# Explore_Labs_GPS_Receiver_ublox_MAX-M8Q.net
KiCad netlist of a schematic drawn in EAGLE
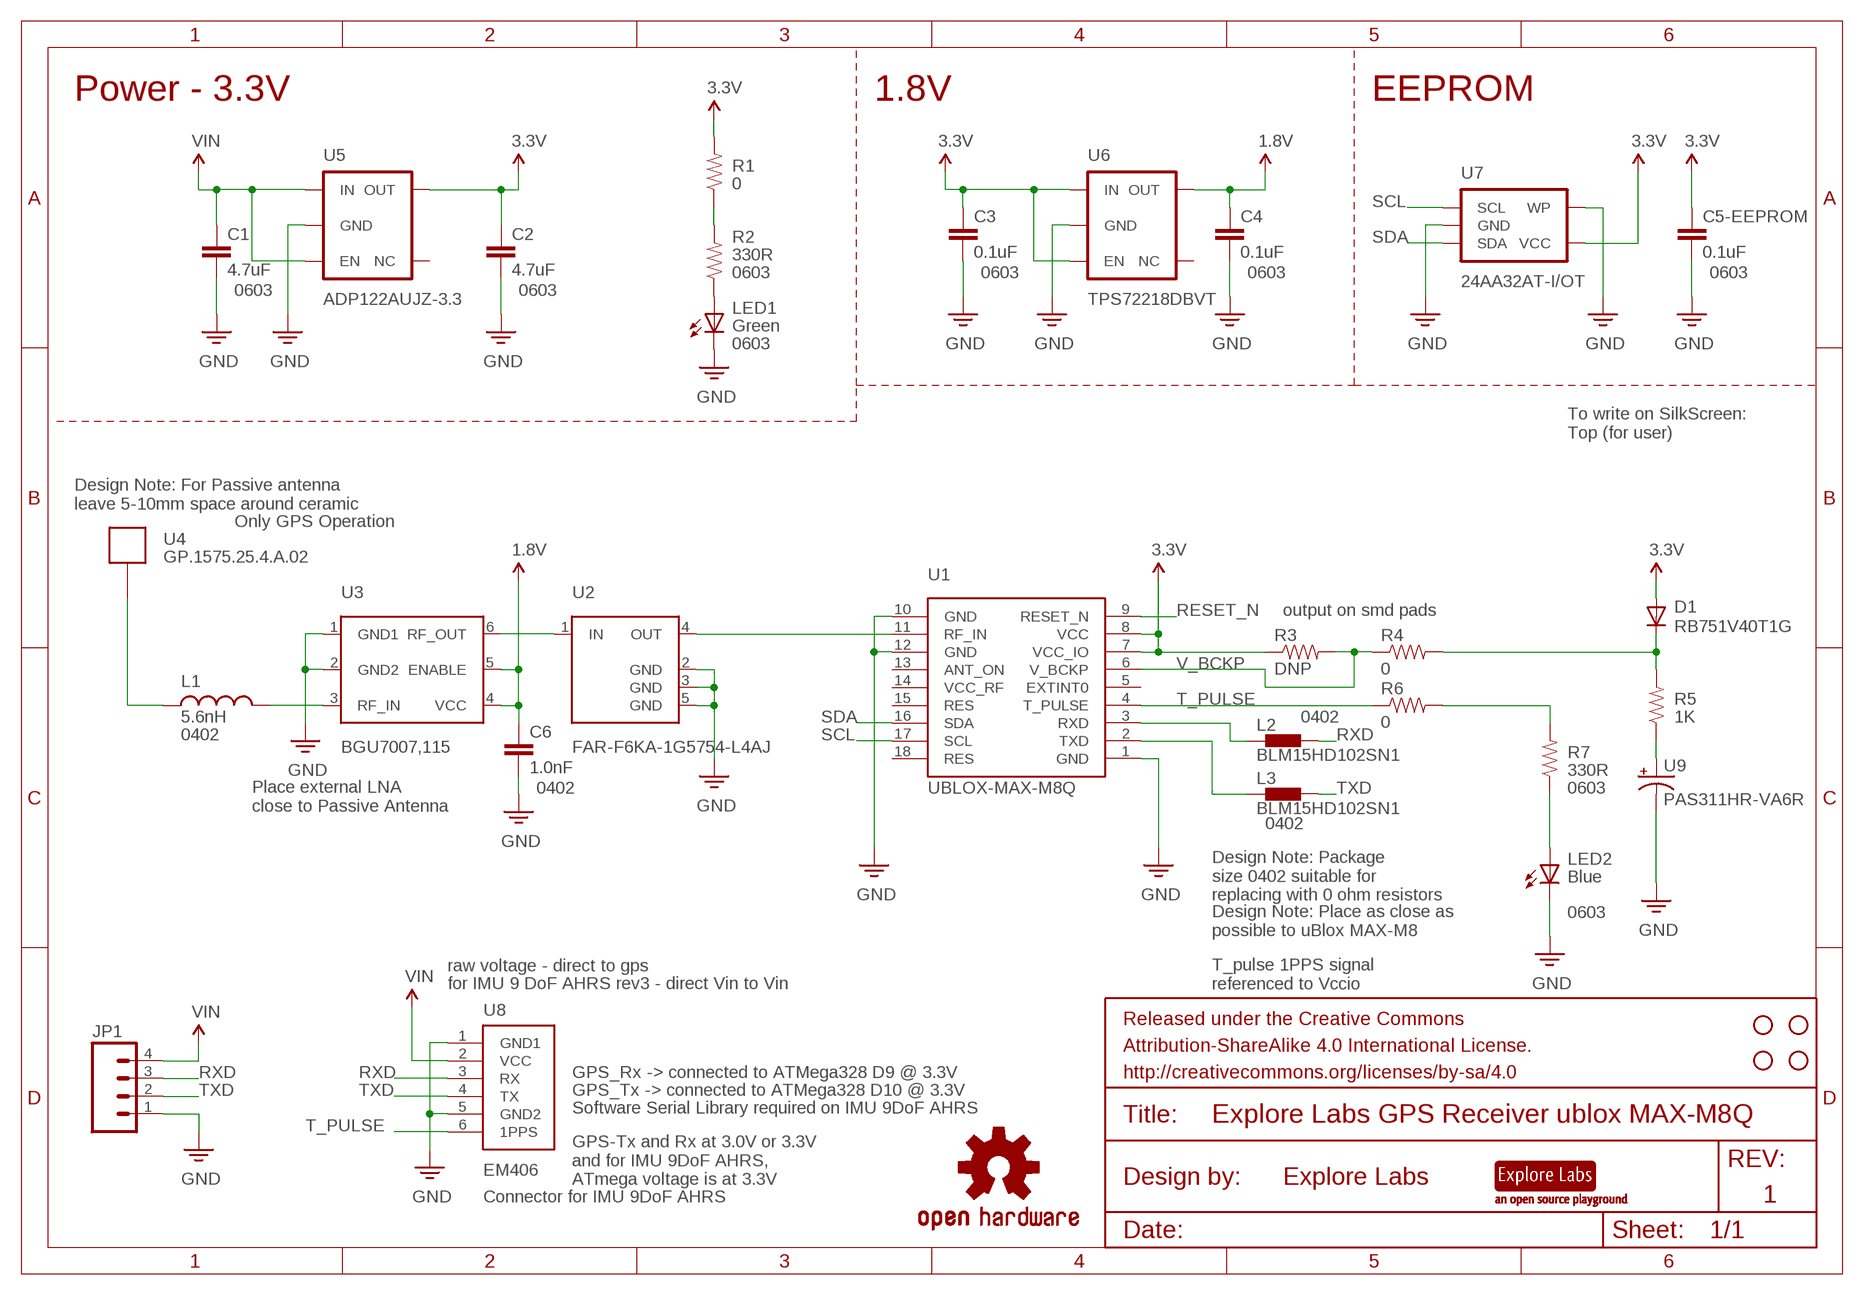
[diagram p0: schematic, sheet 1]

(export (version "E")
  (design (tool "Eeschema 10.0.6"))
  (components
    (comp (ref "C1")
      (value "4.7uF")
      (footprint "eagle-import:0603-CAP")
      (libsource (lib "eagle-import") (part "CAP0603-CAP"))
    )
    (comp (ref "C2")
      (value "4.7uF")
      (footprint "eagle-import:0603-CAP")
      (libsource (lib "eagle-import") (part "CAP0603-CAP"))
    )
    (comp (ref "C3")
      (value "0.1uF")
      (footprint "eagle-import:0603-CAP")
      (libsource (lib "eagle-import") (part "CAP0603-CAP"))
    )
    (comp (ref "C4")
      (value "0.1uF")
      (footprint "eagle-import:0603-CAP")
      (libsource (lib "eagle-import") (part "CAP0603-CAP"))
    )
    (comp (ref "C5-EEPROM")
      (value "0.1uF")
      (footprint "eagle-import:0603-CAP")
      (libsource (lib "eagle-import") (part "CAP0603-CAP"))
    )
    (comp (ref "C6")
      (value "1.0nF")
      (footprint "eagle-import:0402-CAP")
      (libsource (lib "eagle-import") (part "1.0UF-16V-10%(0402)"))
    )
    (comp (ref "D1")
      (value "RB751V40T1G")
      (footprint "eagle-import:SOD-323")
      (libsource (lib "eagle-import") (part "DIODESOD"))
    )
    (comp (ref "JP1")
      (value "M04PTH")
      (footprint "eagle-import:1X04")
      (libsource (lib "eagle-import") (part "M04PTH"))
    )
    (comp (ref "L1")
      (value "5.6nH")
      (footprint "eagle-import:C0402")
      (libsource (lib "eagle-import") (part "INDUCTOR0402"))
    )
    (comp (ref "L2")
      (value "BLM15HD102SN1")
      (footprint "eagle-import:0402-FERRITE")
      (libsource (lib "eagle-import") (part "BLM15HSN1D102"))
    )
    (comp (ref "L3")
      (value "BLM15HD102SN1")
      (footprint "eagle-import:0402-FERRITE")
      (libsource (lib "eagle-import") (part "BLM15HSN1D102"))
    )
    (comp (ref "LED1")
      (value "Green")
      (footprint "eagle-import:CHIP-LED0603")
      (libsource (lib "eagle-import") (part "LEDCHIP-LED0603"))
    )
    (comp (ref "LED2")
      (value "Blue")
      (footprint "eagle-import:CHIP-LED0603")
      (libsource (lib "eagle-import") (part "LEDCHIP-LED0603"))
    )
    (comp (ref "LOGO1")
      (value "OSHW-LOGOTOP")
      (footprint "eagle-import:OSHW-LOGO-M-TOP")
      (libsource (lib "eagle-import") (part "OSHW-LOGOTOP"))
    )
    (comp (ref "LOGO2")
      (value "OSHW-LOGOBOTTOM")
      (footprint "eagle-import:OSHW-LOGO-M-BOTTOM")
      (libsource (lib "eagle-import") (part "OSHW-LOGOBOTTOM"))
    )
    (comp (ref "R1")
      (value "0")
      (footprint "eagle-import:0603-RES")
      (libsource (lib "eagle-import") (part "RESISTOR0603-RES"))
    )
    (comp (ref "R2")
      (value "330R")
      (footprint "eagle-import:0603-RES")
      (libsource (lib "eagle-import") (part "RESISTOR0603-RES"))
    )
    (comp (ref "R3")
      (value "DNP")
      (footprint "eagle-import:0603-RES")
      (libsource (lib "eagle-import") (part "RESISTOR0603-RES"))
    )
    (comp (ref "R4")
      (value "0")
      (footprint "eagle-import:0603-RES")
      (libsource (lib "eagle-import") (part "RESISTOR0603-RES"))
    )
    (comp (ref "R5")
      (value "1K")
      (footprint "eagle-import:0603-RES")
      (libsource (lib "eagle-import") (part "RESISTOR0603-RES"))
    )
    (comp (ref "R6")
      (value "0")
      (footprint "eagle-import:0603-RES")
      (libsource (lib "eagle-import") (part "RESISTOR0603-RES"))
    )
    (comp (ref "R7")
      (value "330R")
      (footprint "eagle-import:0603-RES")
      (libsource (lib "eagle-import") (part "RESISTOR0603-RES"))
    )
    (comp (ref "STANDOFF1")
      (value "STAND-OFF")
      (footprint "eagle-import:STAND-OFF")
      (libsource (lib "eagle-import") (part "STAND-OFF"))
    )
    (comp (ref "STANDOFF2")
      (value "STAND-OFF")
      (footprint "eagle-import:STAND-OFF")
      (libsource (lib "eagle-import") (part "STAND-OFF"))
    )
    (comp (ref "STANDOFF3")
      (value "STAND-OFF")
      (footprint "eagle-import:STAND-OFF")
      (libsource (lib "eagle-import") (part "STAND-OFF"))
    )
    (comp (ref "STANDOFF4")
      (value "STAND-OFF")
      (footprint "eagle-import:STAND-OFF")
      (libsource (lib "eagle-import") (part "STAND-OFF"))
    )
    (comp (ref "U$9")
      (value "EXPLORE-LABS-LOGO")
      (footprint "eagle-import:EXPLORE-LABS-LOGO-TOP")
      (libsource (lib "eagle-import") (part "EXPLORE-LABS-LOGO"))
    )
    (comp (ref "U1")
      (value "UBLOX-MAX-M8Q")
      (footprint "eagle-import:UBLOX-MAX-M8")
      (libsource (lib "eagle-import") (part "UBLOX-MAX-M8Q"))
    )
    (comp (ref "U2")
      (value "FAR-F6KA-1G5754-L4AJ")
      (footprint "eagle-import:QCS5E")
      (libsource (lib "eagle-import") (part "FAR-F6KA-1G5754-L4AJ"))
    )
    (comp (ref "U3")
      (value "BGU7007,115")
      (footprint "eagle-import:SOT886")
      (libsource (lib "eagle-import") (part "BGU7007,115"))
    )
    (comp (ref "U4")
      (value "GP.1575.25.4.A.02")
      (footprint "eagle-import:GP.1575.25.4.A.02")
      (libsource (lib "eagle-import") (part "GP.1575.25.4.A.02"))
    )
    (comp (ref "U5")
      (value "ADP122AUJZ-3.3")
      (footprint "eagle-import:SOT-23-5")
      (libsource (lib "eagle-import") (part "ADP122AUJZ-3.3"))
    )
    (comp (ref "U6")
      (value "TPS72218DBVT")
      (footprint "eagle-import:SOT-23-5")
      (libsource (lib "eagle-import") (part "TPS72218DBVT"))
    )
    (comp (ref "U7")
      (value "24AA32AT-I/OT")
      (footprint "eagle-import:SOT-23-5")
      (libsource (lib "eagle-import") (part "24AA32AT-I/OT"))
    )
    (comp (ref "U8")
      (value "EM406")
      (footprint "eagle-import:EM406")
      (libsource (lib "eagle-import") (part "EM406"))
    )
    (comp (ref "U9")
      (value "PAS311HR-VA6R")
      (footprint "eagle-import:PA311")
      (libsource (lib "eagle-import") (part "PAS311HR-VA6R"))
    )
  )
  (nets
    (net (code "1") (name "/RESET_N") (class "Default")
      (node (ref "U1") (pin "9") (pinfunction "RESET_N_9") (pintype "bidirectional"))
    )
    (net (code "2") (name "/RXD") (class "Default")
      (node (ref "JP1") (pin "3") (pinfunction "3_3") (pintype "passive"))
      (node (ref "L2") (pin "2") (pinfunction "2_2") (pintype "passive"))
      (node (ref "U8") (pin "3") (pinfunction "RX_3") (pintype "bidirectional"))
    )
    (net (code "3") (name "/SCL") (class "Default")
      (node (ref "U1") (pin "17") (pinfunction "SCL_17") (pintype "bidirectional"))
      (node (ref "U7") (pin "1") (pinfunction "SCL_1") (pintype "input"))
    )
    (net (code "4") (name "/SDA") (class "Default")
      (node (ref "U1") (pin "16") (pinfunction "SDA_16") (pintype "bidirectional"))
      (node (ref "U7") (pin "3") (pinfunction "SDA_3") (pintype "bidirectional"))
    )
    (net (code "5") (name "/TXD") (class "Default")
      (node (ref "JP1") (pin "2") (pinfunction "2_2") (pintype "passive"))
      (node (ref "L3") (pin "2") (pinfunction "2_2") (pintype "passive"))
      (node (ref "U8") (pin "4") (pinfunction "TX_4") (pintype "bidirectional"))
    )
    (net (code "6") (name "/T_PULSE") (class "Default")
      (node (ref "R6") (pin "1") (pinfunction "1_1") (pintype "passive"))
      (node (ref "U1") (pin "4") (pinfunction "T_PULSE_4") (pintype "bidirectional"))
      (node (ref "U8") (pin "6") (pinfunction "1PPS_6") (pintype "bidirectional"))
    )
    (net (code "7") (name "/V_BCKP") (class "Default")
      (node (ref "R3") (pin "2") (pinfunction "2_2") (pintype "passive"))
      (node (ref "R4") (pin "1") (pinfunction "1_1") (pintype "passive"))
      (node (ref "U1") (pin "6") (pinfunction "V_BCKP_6") (pintype "bidirectional"))
    )
    (net (code "8") (name "1.8V") (class "Default")
      (node (ref "C4") (pin "1") (pinfunction "1_1") (pintype "passive"))
      (node (ref "C6") (pin "1") (pinfunction "1_1") (pintype "passive"))
      (node (ref "U3") (pin "4") (pinfunction "VCC_4") (pintype "bidirectional"))
      (node (ref "U3") (pin "5") (pinfunction "ENABLE_5") (pintype "bidirectional"))
      (node (ref "U6") (pin "5") (pinfunction "OUT_5") (pintype "power_in"))
    )
    (net (code "9") (name "3.3V") (class "Default")
      (node (ref "C2") (pin "1") (pinfunction "1_1") (pintype "passive"))
      (node (ref "C3") (pin "1") (pinfunction "1_1") (pintype "passive"))
      (node (ref "C5-EEPROM") (pin "1") (pinfunction "1_1") (pintype "passive"))
      (node (ref "D1") (pin "2") (pinfunction "A_2") (pintype "passive"))
      (node (ref "R1") (pin "2") (pinfunction "2_2") (pintype "passive"))
      (node (ref "R3") (pin "1") (pinfunction "1_1") (pintype "passive"))
      (node (ref "U1") (pin "7") (pinfunction "VCC_IO_7") (pintype "bidirectional"))
      (node (ref "U1") (pin "8") (pinfunction "VCC_8") (pintype "bidirectional"))
      (node (ref "U5") (pin "5") (pinfunction "OUT_5") (pintype "power_in"))
      (node (ref "U6") (pin "1") (pinfunction "IN_1") (pintype "power_in"))
      (node (ref "U6") (pin "3") (pinfunction "EN_3") (pintype "input"))
      (node (ref "U7") (pin "4") (pinfunction "VCC_4") (pintype "power_in"))
    )
    (net (code "10") (name "GND") (class "Default")
      (node (ref "C1") (pin "2") (pinfunction "2_2") (pintype "passive"))
      (node (ref "C2") (pin "2") (pinfunction "2_2") (pintype "passive"))
      (node (ref "C3") (pin "2") (pinfunction "2_2") (pintype "passive"))
      (node (ref "C4") (pin "2") (pinfunction "2_2") (pintype "passive"))
      (node (ref "C5-EEPROM") (pin "2") (pinfunction "2_2") (pintype "passive"))
      (node (ref "C6") (pin "2") (pinfunction "2_2") (pintype "passive"))
      (node (ref "JP1") (pin "1") (pinfunction "1_1") (pintype "passive"))
      (node (ref "LED1") (pin "C") (pinfunction "C_C") (pintype "passive"))
      (node (ref "LED2") (pin "C") (pinfunction "C_C") (pintype "passive"))
      (node (ref "U1") (pin "1") (pinfunction "GND_1") (pintype "bidirectional"))
      (node (ref "U1") (pin "10") (pinfunction "GND_10") (pintype "bidirectional"))
      (node (ref "U1") (pin "12") (pinfunction "GND_12") (pintype "bidirectional"))
      (node (ref "U2") (pin "2") (pinfunction "GND_2") (pintype "bidirectional"))
      (node (ref "U2") (pin "3") (pinfunction "GND_3") (pintype "bidirectional"))
      (node (ref "U2") (pin "5") (pinfunction "GND_5") (pintype "bidirectional"))
      (node (ref "U3") (pin "1") (pinfunction "GND1_1") (pintype "bidirectional"))
      (node (ref "U3") (pin "2") (pinfunction "GND2_2") (pintype "bidirectional"))
      (node (ref "U5") (pin "2") (pinfunction "GND_2") (pintype "power_in"))
      (node (ref "U6") (pin "2") (pinfunction "GND_2") (pintype "power_in"))
      (node (ref "U7") (pin "2") (pinfunction "GND_2") (pintype "power_in"))
      (node (ref "U7") (pin "5") (pinfunction "WP_5") (pintype "input"))
      (node (ref "U8") (pin "1") (pinfunction "GND1_1") (pintype "bidirectional"))
      (node (ref "U8") (pin "5") (pinfunction "GND2_5") (pintype "bidirectional"))
      (node (ref "U9") (pin "P$2") (pinfunction "-_P$2") (pintype "passive"))
    )
    (net (code "11") (name "Net-(D1-C)") (class "Default")
      (node (ref "D1") (pin "1") (pinfunction "C_1") (pintype "passive"))
      (node (ref "R4") (pin "2") (pinfunction "2_2") (pintype "passive"))
      (node (ref "R5") (pin "2") (pinfunction "2_2") (pintype "passive"))
    )
    (net (code "12") (name "Net-(LED1-PadA)") (class "Default")
      (node (ref "LED1") (pin "A") (pinfunction "A_A") (pintype "passive"))
      (node (ref "R2") (pin "1") (pinfunction "1_1") (pintype "passive"))
    )
    (net (code "13") (name "Net-(LED2-PadA)") (class "Default")
      (node (ref "LED2") (pin "A") (pinfunction "A_A") (pintype "passive"))
      (node (ref "R7") (pin "1") (pinfunction "1_1") (pintype "passive"))
    )
    (net (code "14") (name "Net-(R1-Pad1)") (class "Default")
      (node (ref "R1") (pin "1") (pinfunction "1_1") (pintype "passive"))
      (node (ref "R2") (pin "2") (pinfunction "2_2") (pintype "passive"))
    )
    (net (code "15") (name "Net-(R6-Pad2)") (class "Default")
      (node (ref "R6") (pin "2") (pinfunction "2_2") (pintype "passive"))
      (node (ref "R7") (pin "2") (pinfunction "2_2") (pintype "passive"))
    )
    (net (code "16") (name "Net-(U1-RF_IN)") (class "Default")
      (node (ref "U1") (pin "11") (pinfunction "RF_IN_11") (pintype "bidirectional"))
      (node (ref "U2") (pin "4") (pinfunction "OUT_4") (pintype "bidirectional"))
    )
    (net (code "17") (name "Net-(U1-RXD)") (class "Default")
      (node (ref "L2") (pin "1") (pinfunction "1_1") (pintype "passive"))
      (node (ref "U1") (pin "3") (pinfunction "RXD_3") (pintype "bidirectional"))
    )
    (net (code "18") (name "Net-(U1-TXD)") (class "Default")
      (node (ref "L3") (pin "1") (pinfunction "1_1") (pintype "passive"))
      (node (ref "U1") (pin "2") (pinfunction "TXD_2") (pintype "bidirectional"))
    )
    (net (code "19") (name "Net-(U2-IN)") (class "Default")
      (node (ref "U2") (pin "1") (pinfunction "IN_1") (pintype "bidirectional"))
      (node (ref "U3") (pin "6") (pinfunction "RF_OUT_6") (pintype "bidirectional"))
    )
    (net (code "20") (name "Net-(U3-RF_IN)") (class "Default")
      (node (ref "L1") (pin "2") (pinfunction "2_2") (pintype "passive"))
      (node (ref "U3") (pin "3") (pinfunction "RF_IN_3") (pintype "bidirectional"))
    )
    (net (code "21") (name "Net-(U4-PIN)") (class "Default")
      (node (ref "L1") (pin "1") (pinfunction "1_1") (pintype "passive"))
      (node (ref "U4") (pin "1") (pinfunction "PIN_1") (pintype "bidirectional"))
    )
    (net (code "22") (name "Net-(U9-+)") (class "Default")
      (node (ref "R5") (pin "1") (pinfunction "1_1") (pintype "passive"))
      (node (ref "U9") (pin "P$1") (pinfunction "+_P$1") (pintype "passive"))
    )
    (net (code "23") (name "VIN") (class "Default")
      (node (ref "C1") (pin "1") (pinfunction "1_1") (pintype "passive"))
      (node (ref "JP1") (pin "4") (pinfunction "4_4") (pintype "passive"))
      (node (ref "U5") (pin "1") (pinfunction "IN_1") (pintype "power_in"))
      (node (ref "U5") (pin "3") (pinfunction "EN_3") (pintype "input"))
      (node (ref "U8") (pin "2") (pinfunction "VCC_2") (pintype "bidirectional"))
    )
    (net (code "24") (name "unconnected-(U1-ANT_ON-Pad13)") (class "Default")
      (node (ref "U1") (pin "13") (pinfunction "ANT_ON_13") (pintype "bidirectional"))
    )
    (net (code "25") (name "unconnected-(U1-EXTINT0-Pad5)") (class "Default")
      (node (ref "U1") (pin "5") (pinfunction "EXTINT0_5") (pintype "bidirectional"))
    )
    (net (code "26") (name "unconnected-(U1-RES-Pad15)") (class "Default")
      (node (ref "U1") (pin "15") (pinfunction "RES_15") (pintype "bidirectional"))
    )
    (net (code "27") (name "unconnected-(U1-RES-Pad18)") (class "Default")
      (node (ref "U1") (pin "18") (pinfunction "RES_18") (pintype "bidirectional"))
    )
    (net (code "28") (name "unconnected-(U1-VCC_RF-Pad14)") (class "Default")
      (node (ref "U1") (pin "14") (pinfunction "VCC_RF_14") (pintype "bidirectional"))
    )
    (net (code "29") (name "unconnected-(U5-NC-Pad4)") (class "Default")
      (node (ref "U5") (pin "4") (pinfunction "NC_4") (pintype "no_connect"))
    )
    (net (code "30") (name "unconnected-(U6-NC-Pad4)") (class "Default")
      (node (ref "U6") (pin "4") (pinfunction "NC_4") (pintype "no_connect"))
    )
  )
)
